# PIANO_ELISE_01.net
KiCad netlist of a schematic drawn in Altium Designer
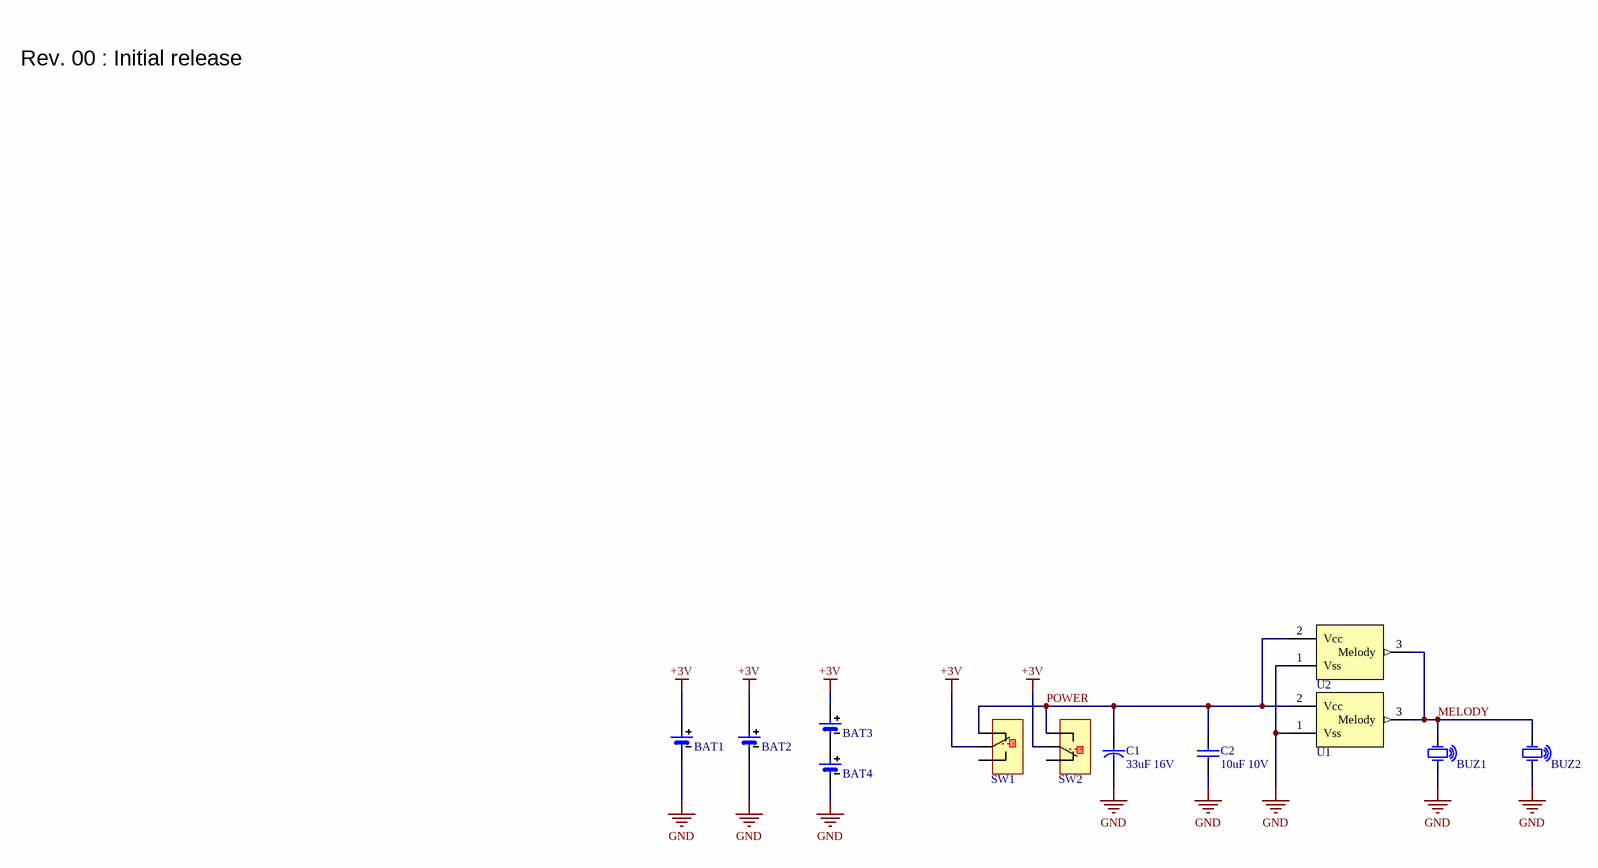
[diagram p0: PIANO_ELISE_01.SchDoc]

(export (version "E")
  (design (tool "Eeschema 10.0.6"))
  (components
    (comp (ref "BAT1")
      (value "CR2032 Battery Holder")
      (footprint "BAT_CR2032")
      (description "=Description")
      (libsource (lib "Phyx_Components") (part "BAT_2"))
    )
    (comp (ref "BAT2")
      (value "CR2032 SMD Battery Holder")
      (footprint "BAT_CR2032_KEY_1060")
      (description "=Description")
      (libsource (lib "Phyx_Components") (part "BAT_2"))
    )
    (comp (ref "BAT3")
      (value "Single AAA battery holder")
      (footprint "KEY_2466")
      (description "=Description")
      (libsource (lib "Phyx_Components") (part "BAT_2"))
    )
    (comp (ref "BAT4")
      (value "Single AAA battery holder")
      (footprint "KEY_2466")
      (description "=Description")
      (libsource (lib "Phyx_Components") (part "BAT_2"))
    )
    (comp (ref "BUZ1")
      (value "12x12x3mm Piezo Buzzer Transducer 81dB")
      (footprint "CUI_CMT-1203-SMT")
      (description "Crystal Oscillator")
      (libsource (lib "Phyx_Components") (part "Buzzer"))
    )
    (comp (ref "BUZ2")
      (value "14x14x7mm Piezo Buzzer Transducer 80dB")
      (footprint "CUI_CEP-1162")
      (description "Crystal Oscillator")
      (libsource (lib "Phyx_Components") (part "Buzzer"))
    )
    (comp (ref "C1")
      (value "33uF 16V")
      (footprint "C_4x7_1.5mm")
      (description "Capacitor electrolyt")
      (fields (field (name "Comment") "CAP_POL"))
      (libsource (lib "Phyx_Components") (part "CAP_POL"))
    )
    (comp (ref "C2")
      (value "10uF 10V")
      (footprint "C0805_N")
      (description "Capacitor Ceramic")
      (fields (field (name "Comment") "CAP_CERAMIC"))
      (libsource (lib "Phyx_Components") (part "CAP_CERAMIC"))
    )
    (comp (ref "SW1")
      (value "XKB Connectivity DM1-135P-1-16 Micro Switch 12.7mm 0.1A 30V")
      (footprint "WE_463092370402")
      (libsource (lib "Phyx_Components") (part "SW_1P2T"))
    )
    (comp (ref "SW2")
      (value "XKB Connectivity DM1-135P-1-16 Micro Switch 12.7mm 0.1A 30V")
      (footprint "WE_463092370402")
      (libsource (lib "") (part "SW_1P2T_1"))
    )
    (comp (ref "U1")
      (value "UM66T - Fur Elise")
      (footprint "TO-92A")
      (description "=Description")
      (libsource (lib "Phyx_Components") (part "UM66T-xxL"))
    )
    (comp (ref "U2")
      (value "UM66T - Fur Elise")
      (footprint "TO-92A_WIDE")
      (description "=Description")
      (libsource (lib "Phyx_Components") (part "UM66T-xxL"))
    )
  )
  (nets
    (net (code "1") (name "+3V") (class "Default")
      (node (ref "BAT1") (pin "1") (pinfunction "1_1") (pintype "passive"))
      (node (ref "BAT2") (pin "1") (pinfunction "1_1") (pintype "passive"))
      (node (ref "BAT3") (pin "1") (pinfunction "1_1") (pintype "passive"))
      (node (ref "SW1") (pin "2") (pinfunction "2_2") (pintype "passive"))
      (node (ref "SW2") (pin "2") (pinfunction "2_2") (pintype "passive"))
    )
    (net (code "2") (name "/MELODY") (class "Default")
      (node (ref "BUZ1") (pin "1") (pinfunction "OSC1_1") (pintype "passive"))
      (node (ref "BUZ2") (pin "1") (pinfunction "OSC1_1") (pintype "passive"))
      (node (ref "U1") (pin "3") (pinfunction "Melody_3") (pintype "output"))
      (node (ref "U2") (pin "3") (pinfunction "Melody_3") (pintype "output"))
    )
    (net (code "3") (name "/POWER") (class "Default")
      (node (ref "C1") (pin "1") (pinfunction "1_1") (pintype "passive"))
      (node (ref "C2") (pin "1") (pinfunction "1_1") (pintype "passive"))
      (node (ref "SW1") (pin "1") (pinfunction "1_1") (pintype "passive"))
      (node (ref "SW2") (pin "3") (pinfunction "3_3") (pintype "passive"))
      (node (ref "U1") (pin "2") (pinfunction "Vcc_2") (pintype "power_in"))
      (node (ref "U2") (pin "2") (pinfunction "Vcc_2") (pintype "power_in"))
    )
    (net (code "4") (name "GND") (class "Default")
      (node (ref "BAT1") (pin "2") (pinfunction "2_2") (pintype "passive"))
      (node (ref "BAT2") (pin "2") (pinfunction "2_2") (pintype "passive"))
      (node (ref "BAT4") (pin "2") (pinfunction "2_2") (pintype "passive"))
      (node (ref "BUZ1") (pin "2") (pinfunction "OSC2_2") (pintype "passive"))
      (node (ref "BUZ2") (pin "2") (pinfunction "OSC2_2") (pintype "passive"))
      (node (ref "C1") (pin "2") (pinfunction "2_2") (pintype "passive"))
      (node (ref "C2") (pin "2") (pinfunction "2_2") (pintype "passive"))
      (node (ref "U1") (pin "1") (pinfunction "Vss_1") (pintype "power_in"))
      (node (ref "U2") (pin "1") (pinfunction "Vss_1") (pintype "power_in"))
    )
    (net (code "5") (name "Net-(BAT3-Pad2)") (class "Default")
      (node (ref "BAT3") (pin "2") (pinfunction "2_2") (pintype "passive"))
      (node (ref "BAT4") (pin "1") (pinfunction "1_1") (pintype "passive"))
    )
    (net (code "6") (name "unconnected-(SW1-Pad3)") (class "Default")
      (node (ref "SW1") (pin "3") (pinfunction "3_3") (pintype "passive"))
    )
    (net (code "7") (name "unconnected-(SW2-Pad1)") (class "Default")
      (node (ref "SW2") (pin "1") (pinfunction "1_1") (pintype "passive"))
    )
  )
)
